# TRD.net
KiCad netlist of a schematic drawn in Altium Designer
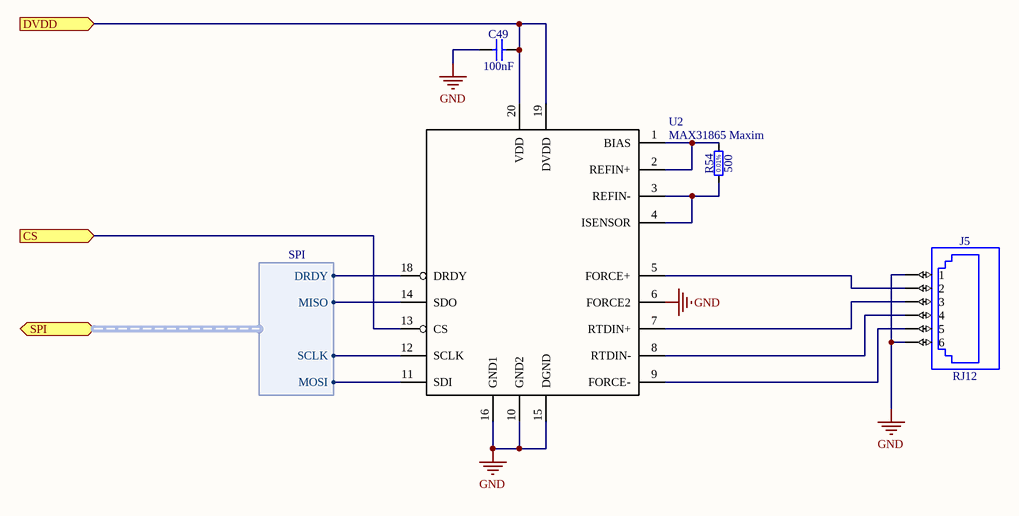
[diagram p0: TRD.SchDoc]

(export (version "E")
  (design (tool "Eeschema 10.0.6"))
  (components
    (comp (ref "C49")
      (value "100nF")
      (footprint "CAPC2012X135N")
      (description "Non-polarised capacitor")
      (fields
        (field (name "PART NUMBER") "CC0805_100NF_50V_10%_X7R")
        (field (name "VOLTAGE") "50V")
        (field (name "AUTHOR") "CERN DEM JLC")
      )
      (libsource (lib "Capacitors") (part "Capacitor - non polarized"))
    )
    (comp (ref "J5")
      (value "RJ12")
      (footprint "WURTH_615006138521")
      (description "Connector RJ12 (6P6C)")
      (fields
        (field (name "PART NUMBER") "WURTH_615006138521")
        (field (name "MANUFACTURER") "WURTH ELEKTRONIK")
        (field (name "AUTHOR") "CERN DEM MR")
      )
      (libsource (lib "Connectors") (part "Connector RJ12"))
    )
    (comp (ref "R54")
      (value "500")
      (footprint "RESC2013X64N")
      (description "Resistor - 0.01%")
      (fields
        (field (name "PART NUMBER") "R0805_500R_0.01%_0.2W_0.2PPM_VISHAY_VSMP")
        (field (name "POWER") "0.2W")
        (field (name "AUTHOR") "CERN DEM JLC")
      )
      (libsource (lib "Resistors") (part "Resistor - 0.01%"))
    )
    (comp (ref "U2")
      (value "MAX31865 Maxim")
      (footprint "QFN65P500X500X80-21N-S335")
      (fields (field (name "MANUFACTURER") "Maxim"))
      (libsource (lib "Additional") (part "MAX31865"))
    )
  )
  (nets
    (net (code "2") (name "/CS") (class "Default")
      (node (ref "U2") (pin "13") (pinfunction "CS_13") (pintype "passive"))
    )
    (net (code "3") (name "/DRDY") (class "Default")
      (node (ref "U2") (pin "18") (pinfunction "DRDY_18") (pintype "passive"))
    )
    (net (code "4") (name "/DVDD") (class "Default")
      (node (ref "C49") (pin "2") (pinfunction "2_2") (pintype "passive"))
      (node (ref "U2") (pin "19") (pinfunction "DVDD_19") (pintype "passive"))
      (node (ref "U2") (pin "20") (pinfunction "VDD_20") (pintype "passive"))
    )
    (net (code "5") (name "/MISO") (class "Default")
      (node (ref "U2") (pin "14") (pinfunction "SDO_14") (pintype "passive"))
    )
    (net (code "6") (name "/MOSI") (class "Default")
      (node (ref "U2") (pin "11") (pinfunction "SDI_11") (pintype "passive"))
    )
    (net (code "7") (name "/SCLK") (class "Default")
      (node (ref "U2") (pin "12") (pinfunction "SCLK_12") (pintype "passive"))
    )
    (net (code "9") (name "GND") (class "Default")
      (node (ref "C49") (pin "1") (pinfunction "1_1") (pintype "passive"))
      (node (ref "J5") (pin "1") (pinfunction "1_1") (pintype "bidirectional"))
      (node (ref "J5") (pin "6") (pinfunction "6_6") (pintype "bidirectional"))
      (node (ref "U2") (pin "10") (pinfunction "GND2_10") (pintype "passive"))
      (node (ref "U2") (pin "15") (pinfunction "DGND_15") (pintype "passive"))
      (node (ref "U2") (pin "16") (pinfunction "GND1_16") (pintype "passive"))
      (node (ref "U2") (pin "6") (pinfunction "FORCE2_6") (pintype "passive"))
    )
    (net (code "10") (name "Net-(U2-BIAS)") (class "Default")
      (node (ref "R54") (pin "2") (pinfunction "2_2") (pintype "passive"))
      (node (ref "U2") (pin "1") (pinfunction "BIAS_1") (pintype "passive"))
      (node (ref "U2") (pin "2") (pinfunction "REFIN+_2") (pintype "passive"))
    )
    (net (code "11") (name "Net-(U2-FORCE+)") (class "Default")
      (node (ref "J5") (pin "2") (pinfunction "2_2") (pintype "bidirectional"))
      (node (ref "U2") (pin "5") (pinfunction "FORCE+_5") (pintype "passive"))
    )
    (net (code "12") (name "Net-(U2-FORCE-)") (class "Default")
      (node (ref "J5") (pin "5") (pinfunction "5_5") (pintype "bidirectional"))
      (node (ref "U2") (pin "9") (pinfunction "FORCE-_9") (pintype "passive"))
    )
    (net (code "13") (name "Net-(U2-ISENSOR)") (class "Default")
      (node (ref "R54") (pin "1") (pinfunction "1_1") (pintype "passive"))
      (node (ref "U2") (pin "3") (pinfunction "REFIN-_3") (pintype "passive"))
      (node (ref "U2") (pin "4") (pinfunction "ISENSOR_4") (pintype "passive"))
    )
    (net (code "14") (name "Net-(U2-RTDIN+)") (class "Default")
      (node (ref "J5") (pin "3") (pinfunction "3_3") (pintype "bidirectional"))
      (node (ref "U2") (pin "7") (pinfunction "RTDIN+_7") (pintype "passive"))
    )
    (net (code "15") (name "Net-(U2-RTDIN-)") (class "Default")
      (node (ref "J5") (pin "4") (pinfunction "4_4") (pintype "bidirectional"))
      (node (ref "U2") (pin "8") (pinfunction "RTDIN-_8") (pintype "passive"))
    )
    (net (code "16") (name "unconnected-(U2-Pad17)") (class "Default")
      (node (ref "U2") (pin "17") (pintype "passive"))
    )
  )
)
